# Monster_Moto_Shield.net
KiCad netlist of a schematic drawn in EAGLE
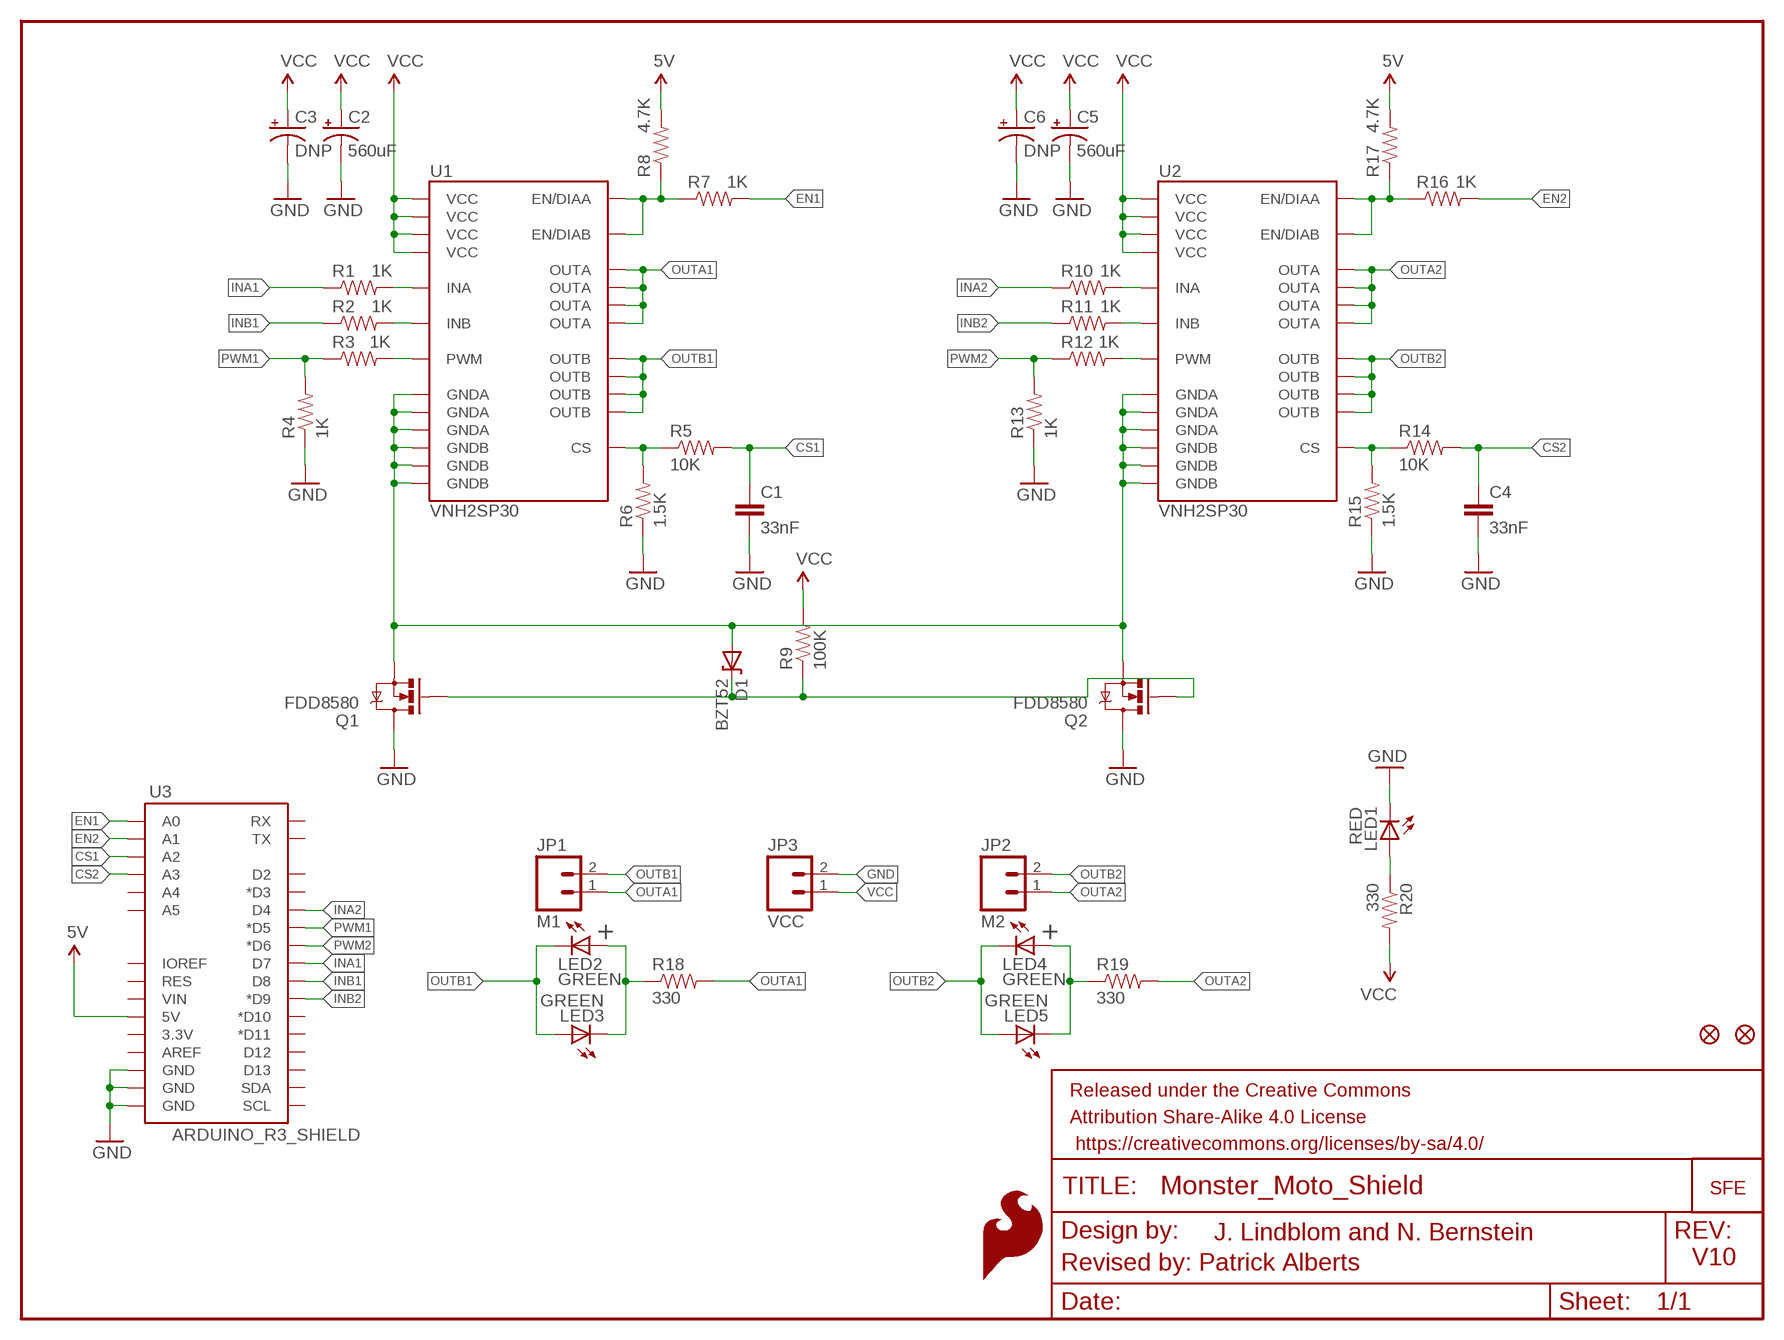
[diagram p0: schematic, sheet 1]

(export (version "E")
  (design (tool "Eeschema 10.0.6"))
  (components
    (comp (ref "C1")
      (value "33nF")
      (footprint "eagle-import:0603-CAP")
      (libsource (lib "eagle-import") (part "CAP0603-CAP"))
    )
    (comp (ref "C2")
      (value "560uF")
      (footprint "eagle-import:PANASONIC_G")
      (libsource (lib "eagle-import") (part "CAP_POLG"))
    )
    (comp (ref "C3")
      (value "DNP")
      (footprint "eagle-import:CPOL-RADIAL-1000UF-25V")
      (libsource (lib "eagle-import") (part "CAP_POLPTH4"))
    )
    (comp (ref "C4")
      (value "33nF")
      (footprint "eagle-import:0603-CAP")
      (libsource (lib "eagle-import") (part "CAP0603-CAP"))
    )
    (comp (ref "C5")
      (value "560uF")
      (footprint "eagle-import:PANASONIC_G")
      (libsource (lib "eagle-import") (part "CAP_POLG"))
    )
    (comp (ref "C6")
      (value "DNP")
      (footprint "eagle-import:CPOL-RADIAL-1000UF-25V")
      (libsource (lib "eagle-import") (part "CAP_POLPTH4"))
    )
    (comp (ref "D1")
      (value "BZT52")
      (footprint "eagle-import:SOD-323")
      (libsource (lib "eagle-import") (part "DIODE-ZENER-BZT52"))
    )
    (comp (ref "FRAME*")
      (value "FRAME-LETTER")
      (footprint "eagle-import:CREATIVE_COMMONS")
      (libsource (lib "eagle-import") (part "FRAME-LETTER"))
    )
    (comp (ref "JP1")
      (value "M1")
      (footprint "eagle-import:1X02_XTRA_BIG")
      (libsource (lib "eagle-import") (part "M02PTH4"))
    )
    (comp (ref "JP2")
      (value "M2")
      (footprint "eagle-import:1X02_XTRA_BIG")
      (libsource (lib "eagle-import") (part "M02PTH4"))
    )
    (comp (ref "JP3")
      (value "VCC")
      (footprint "eagle-import:1X02_XTRA_BIG")
      (libsource (lib "eagle-import") (part "M02PTH4"))
    )
    (comp (ref "JP4")
      (value "FIDUCIAL1X2")
      (footprint "eagle-import:FIDUCIAL-1X2")
      (libsource (lib "eagle-import") (part "FIDUCIAL1X2"))
    )
    (comp (ref "JP5")
      (value "LOGO-SFENEW")
      (footprint "eagle-import:SFE-NEW-WEBLOGO")
      (libsource (lib "eagle-import") (part "LOGO-SFENEW"))
    )
    (comp (ref "JP6")
      (value "FIDUCIAL1X2")
      (footprint "eagle-import:FIDUCIAL-1X2")
      (libsource (lib "eagle-import") (part "FIDUCIAL1X2"))
    )
    (comp (ref "LED1")
      (value "RED")
      (footprint "eagle-import:LED-0603")
      (libsource (lib "eagle-import") (part "LED-RED0603"))
    )
    (comp (ref "LED2")
      (value "GREEN")
      (footprint "eagle-import:LED-0603")
      (libsource (lib "eagle-import") (part "LED-GREEN0603"))
    )
    (comp (ref "LED3")
      (value "GREEN")
      (footprint "eagle-import:LED-0603")
      (libsource (lib "eagle-import") (part "LED-GREEN0603"))
    )
    (comp (ref "LED4")
      (value "GREEN")
      (footprint "eagle-import:LED-0603")
      (libsource (lib "eagle-import") (part "LED-GREEN0603"))
    )
    (comp (ref "LED5")
      (value "GREEN")
      (footprint "eagle-import:LED-0603")
      (libsource (lib "eagle-import") (part "LED-GREEN0603"))
    )
    (comp (ref "LOGO1")
      (value "SFE_LOGO_FLAME.2_INCH")
      (footprint "eagle-import:SFE_LOGO_FLAME_.2")
      (libsource (lib "eagle-import") (part "SFE_LOGO_FLAME.2_INCH"))
    )
    (comp (ref "Q1")
      (value "FDD8580")
      (footprint "eagle-import:DPAK")
      (libsource (lib "eagle-import") (part "MOSFET-NCHANNELFDD8580"))
    )
    (comp (ref "Q2")
      (value "FDD8580")
      (footprint "eagle-import:DPAK")
      (libsource (lib "eagle-import") (part "MOSFET-NCHANNELFDD8580"))
    )
    (comp (ref "R1")
      (value "1K")
      (footprint "eagle-import:0603-RES")
      (libsource (lib "eagle-import") (part "1KOHM1/10W1%(0603)"))
    )
    (comp (ref "R2")
      (value "1K")
      (footprint "eagle-import:0603-RES")
      (libsource (lib "eagle-import") (part "1KOHM1/10W1%(0603)"))
    )
    (comp (ref "R3")
      (value "1K")
      (footprint "eagle-import:0603-RES")
      (libsource (lib "eagle-import") (part "1KOHM1/10W1%(0603)"))
    )
    (comp (ref "R4")
      (value "1K")
      (footprint "eagle-import:0603-RES")
      (libsource (lib "eagle-import") (part "1KOHM1/10W1%(0603)"))
    )
    (comp (ref "R5")
      (value "10K")
      (footprint "eagle-import:0603-RES")
      (libsource (lib "eagle-import") (part "10KOHM1/10W1%(0603)0603"))
    )
    (comp (ref "R6")
      (value "1.5K")
      (footprint "eagle-import:0603")
      (libsource (lib "eagle-import") (part "1.5KOHM1/10W1%(0603)"))
    )
    (comp (ref "R7")
      (value "1K")
      (footprint "eagle-import:0603-RES")
      (libsource (lib "eagle-import") (part "1KOHM1/10W1%(0603)"))
    )
    (comp (ref "R8")
      (value "4.7K")
      (footprint "eagle-import:0603")
      (libsource (lib "eagle-import") (part "4.7KOHM1/10W1%(0603)"))
    )
    (comp (ref "R9")
      (value "100K")
      (footprint "eagle-import:0603-RES")
      (libsource (lib "eagle-import") (part "100KOHM1/10W1%(0603)"))
    )
    (comp (ref "R10")
      (value "1K")
      (footprint "eagle-import:0603-RES")
      (libsource (lib "eagle-import") (part "1KOHM1/10W1%(0603)"))
    )
    (comp (ref "R11")
      (value "1K")
      (footprint "eagle-import:0603-RES")
      (libsource (lib "eagle-import") (part "1KOHM1/10W1%(0603)"))
    )
    (comp (ref "R12")
      (value "1K")
      (footprint "eagle-import:0603-RES")
      (libsource (lib "eagle-import") (part "1KOHM1/10W1%(0603)"))
    )
    (comp (ref "R13")
      (value "1K")
      (footprint "eagle-import:0603-RES")
      (libsource (lib "eagle-import") (part "1KOHM1/10W1%(0603)"))
    )
    (comp (ref "R14")
      (value "10K")
      (footprint "eagle-import:0603-RES")
      (libsource (lib "eagle-import") (part "10KOHM1/10W1%(0603)0603"))
    )
    (comp (ref "R15")
      (value "1.5K")
      (footprint "eagle-import:0603")
      (libsource (lib "eagle-import") (part "1.5KOHM1/10W1%(0603)"))
    )
    (comp (ref "R16")
      (value "1K")
      (footprint "eagle-import:0603-RES")
      (libsource (lib "eagle-import") (part "1KOHM1/10W1%(0603)"))
    )
    (comp (ref "R17")
      (value "4.7K")
      (footprint "eagle-import:0603")
      (libsource (lib "eagle-import") (part "4.7KOHM1/10W1%(0603)"))
    )
    (comp (ref "R18")
      (value "330")
      (footprint "eagle-import:0603")
      (libsource (lib "eagle-import") (part "33OHM1/10W1%(0603)"))
    )
    (comp (ref "R19")
      (value "330")
      (footprint "eagle-import:0603")
      (libsource (lib "eagle-import") (part "33OHM1/10W1%(0603)"))
    )
    (comp (ref "R20")
      (value "330")
      (footprint "eagle-import:0603")
      (libsource (lib "eagle-import") (part "33OHM1/10W1%(0603)"))
    )
    (comp (ref "U1")
      (value "VNH2SP30")
      (footprint "eagle-import:VNH2SP30")
      (libsource (lib "eagle-import") (part "VNH2SP30"))
    )
    (comp (ref "U2")
      (value "VNH2SP30")
      (footprint "eagle-import:VNH2SP30")
      (libsource (lib "eagle-import") (part "VNH2SP30"))
    )
    (comp (ref "U3")
      (value "ARDUINO_R3_SHIELD")
      (footprint "eagle-import:UNO_R3_SHIELD")
      (libsource (lib "eagle-import") (part "ARDUINO_R3_SHIELD"))
    )
  )
  (nets
    (net (code "1") (name "5V") (class "Default")
      (node (ref "R17") (pin "2") (pinfunction "2_2") (pintype "passive"))
      (node (ref "R8") (pin "2") (pinfunction "2_2") (pintype "passive"))
      (node (ref "U3") (pin "5V") (pinfunction "5V_5V") (pintype "bidirectional"))
    )
    (net (code "2") (name "CS1") (class "Default")
      (node (ref "C1") (pin "1") (pinfunction "1_1") (pintype "passive"))
      (node (ref "R5") (pin "2") (pinfunction "2_2") (pintype "passive"))
      (node (ref "U3") (pin "A2") (pinfunction "A2_A2") (pintype "bidirectional"))
    )
    (net (code "3") (name "CS2") (class "Default")
      (node (ref "C4") (pin "1") (pinfunction "1_1") (pintype "passive"))
      (node (ref "R14") (pin "2") (pinfunction "2_2") (pintype "passive"))
      (node (ref "U3") (pin "A3") (pinfunction "A3_A3") (pintype "bidirectional"))
    )
    (net (code "4") (name "EN1") (class "Default")
      (node (ref "R7") (pin "2") (pinfunction "2_2") (pintype "passive"))
      (node (ref "U3") (pin "A0") (pinfunction "A0_A0") (pintype "bidirectional"))
    )
    (net (code "5") (name "EN2") (class "Default")
      (node (ref "R16") (pin "2") (pinfunction "2_2") (pintype "passive"))
      (node (ref "U3") (pin "A1") (pinfunction "A1_A1") (pintype "bidirectional"))
    )
    (net (code "6") (name "GND") (class "Default")
      (node (ref "C1") (pin "2") (pinfunction "2_2") (pintype "passive"))
      (node (ref "C2") (pin "-") (pinfunction "-_-") (pintype "passive"))
      (node (ref "C3") (pin "2") (pinfunction "-_2") (pintype "passive"))
      (node (ref "C4") (pin "2") (pinfunction "2_2") (pintype "passive"))
      (node (ref "C5") (pin "-") (pinfunction "-_-") (pintype "passive"))
      (node (ref "C6") (pin "2") (pinfunction "-_2") (pintype "passive"))
      (node (ref "JP3") (pin "2") (pinfunction "2_2") (pintype "passive"))
      (node (ref "LED1") (pin "C") (pinfunction "C_C") (pintype "passive"))
      (node (ref "Q1") (pin "4") (pinfunction "D_4") (pintype "passive"))
      (node (ref "Q2") (pin "4") (pinfunction "D_4") (pintype "passive"))
      (node (ref "R13") (pin "1") (pinfunction "1_1") (pintype "passive"))
      (node (ref "R15") (pin "1") (pinfunction "1_1") (pintype "passive"))
      (node (ref "R4") (pin "1") (pinfunction "1_1") (pintype "passive"))
      (node (ref "R6") (pin "1") (pinfunction "1_1") (pintype "passive"))
      (node (ref "U3") (pin "GND@0") (pinfunction "GND_GND@0") (pintype "bidirectional"))
      (node (ref "U3") (pin "GND@1") (pinfunction "GND_GND@1") (pintype "bidirectional"))
      (node (ref "U3") (pin "GND@2") (pinfunction "GND_GND@2") (pintype "bidirectional"))
    )
    (net (code "7") (name "INA1") (class "Default")
      (node (ref "R1") (pin "1") (pinfunction "1_1") (pintype "passive"))
      (node (ref "U3") (pin "D7") (pinfunction "D7_D7") (pintype "bidirectional"))
    )
    (net (code "8") (name "INA2") (class "Default")
      (node (ref "R10") (pin "1") (pinfunction "1_1") (pintype "passive"))
      (node (ref "U3") (pin "D4") (pinfunction "D4_D4") (pintype "bidirectional"))
    )
    (net (code "9") (name "INB1") (class "Default")
      (node (ref "R2") (pin "1") (pinfunction "1_1") (pintype "passive"))
      (node (ref "U3") (pin "D8") (pinfunction "D8_D8") (pintype "bidirectional"))
    )
    (net (code "10") (name "INB2") (class "Default")
      (node (ref "R11") (pin "1") (pinfunction "1_1") (pintype "passive"))
      (node (ref "U3") (pin "D9") (pinfunction "*D9_D9") (pintype "bidirectional"))
    )
    (net (code "11") (name "Net-(D1-A)") (class "Default")
      (node (ref "D1") (pin "2") (pinfunction "A_2") (pintype "passive"))
      (node (ref "Q1") (pin "3") (pinfunction "S_3") (pintype "passive"))
      (node (ref "Q2") (pin "3") (pinfunction "S_3") (pintype "passive"))
      (node (ref "U1") (pin "18") (pinfunction "GNDB_18") (pintype "bidirectional"))
      (node (ref "U1") (pin "19") (pinfunction "GNDB_19") (pintype "bidirectional"))
      (node (ref "U1") (pin "20") (pinfunction "GNDB_20") (pintype "bidirectional"))
      (node (ref "U1") (pin "26") (pinfunction "GNDA_26") (pintype "bidirectional"))
      (node (ref "U1") (pin "27") (pinfunction "GNDA_27") (pintype "bidirectional"))
      (node (ref "U1") (pin "28") (pinfunction "GNDA_28") (pintype "bidirectional"))
      (node (ref "U2") (pin "18") (pinfunction "GNDB_18") (pintype "bidirectional"))
      (node (ref "U2") (pin "19") (pinfunction "GNDB_19") (pintype "bidirectional"))
      (node (ref "U2") (pin "20") (pinfunction "GNDB_20") (pintype "bidirectional"))
      (node (ref "U2") (pin "26") (pinfunction "GNDA_26") (pintype "bidirectional"))
      (node (ref "U2") (pin "27") (pinfunction "GNDA_27") (pintype "bidirectional"))
      (node (ref "U2") (pin "28") (pinfunction "GNDA_28") (pintype "bidirectional"))
    )
    (net (code "12") (name "Net-(D1-C)") (class "Default")
      (node (ref "D1") (pin "1") (pinfunction "C_1") (pintype "passive"))
      (node (ref "Q1") (pin "1") (pinfunction "G_1") (pintype "passive"))
      (node (ref "Q2") (pin "1") (pinfunction "G_1") (pintype "passive"))
      (node (ref "R9") (pin "1") (pinfunction "1_1") (pintype "passive"))
    )
    (net (code "13") (name "Net-(LED1-PadA)") (class "Default")
      (node (ref "LED1") (pin "A") (pinfunction "A_A") (pintype "passive"))
      (node (ref "R20") (pin "1") (pinfunction "1_1") (pintype "passive"))
    )
    (net (code "14") (name "Net-(LED2-PadA)") (class "Default")
      (node (ref "LED2") (pin "A") (pinfunction "A_A") (pintype "passive"))
      (node (ref "LED3") (pin "C") (pinfunction "C_C") (pintype "passive"))
      (node (ref "R18") (pin "1") (pinfunction "1_1") (pintype "passive"))
    )
    (net (code "15") (name "Net-(LED4-PadA)") (class "Default")
      (node (ref "LED4") (pin "A") (pinfunction "A_A") (pintype "passive"))
      (node (ref "LED5") (pin "C") (pinfunction "C_C") (pintype "passive"))
      (node (ref "R19") (pin "1") (pinfunction "1_1") (pintype "passive"))
    )
    (net (code "16") (name "Net-(U1-CS)") (class "Default")
      (node (ref "R5") (pin "1") (pinfunction "1_1") (pintype "passive"))
      (node (ref "R6") (pin "2") (pinfunction "2_2") (pintype "passive"))
      (node (ref "U1") (pin "9") (pinfunction "CS_9") (pintype "bidirectional"))
    )
    (net (code "17") (name "Net-(U1-EN{slash}DIAA)") (class "Default")
      (node (ref "R7") (pin "1") (pinfunction "1_1") (pintype "passive"))
      (node (ref "R8") (pin "1") (pinfunction "1_1") (pintype "passive"))
      (node (ref "U1") (pin "10") (pinfunction "EN/DIAB_10") (pintype "bidirectional"))
      (node (ref "U1") (pin "6") (pinfunction "EN/DIAA_6") (pintype "bidirectional"))
    )
    (net (code "18") (name "Net-(U1-INA)") (class "Default")
      (node (ref "R1") (pin "2") (pinfunction "2_2") (pintype "passive"))
      (node (ref "U1") (pin "5") (pinfunction "INA_5") (pintype "bidirectional"))
    )
    (net (code "19") (name "Net-(U1-INB)") (class "Default")
      (node (ref "R2") (pin "2") (pinfunction "2_2") (pintype "passive"))
      (node (ref "U1") (pin "11") (pinfunction "INB_11") (pintype "bidirectional"))
    )
    (net (code "20") (name "Net-(U1-PWM)") (class "Default")
      (node (ref "R3") (pin "2") (pinfunction "2_2") (pintype "passive"))
      (node (ref "U1") (pin "8") (pinfunction "PWM_8") (pintype "bidirectional"))
    )
    (net (code "21") (name "Net-(U2-CS)") (class "Default")
      (node (ref "R14") (pin "1") (pinfunction "1_1") (pintype "passive"))
      (node (ref "R15") (pin "2") (pinfunction "2_2") (pintype "passive"))
      (node (ref "U2") (pin "9") (pinfunction "CS_9") (pintype "bidirectional"))
    )
    (net (code "22") (name "Net-(U2-EN{slash}DIAA)") (class "Default")
      (node (ref "R16") (pin "1") (pinfunction "1_1") (pintype "passive"))
      (node (ref "R17") (pin "1") (pinfunction "1_1") (pintype "passive"))
      (node (ref "U2") (pin "10") (pinfunction "EN/DIAB_10") (pintype "bidirectional"))
      (node (ref "U2") (pin "6") (pinfunction "EN/DIAA_6") (pintype "bidirectional"))
    )
    (net (code "23") (name "Net-(U2-INA)") (class "Default")
      (node (ref "R10") (pin "2") (pinfunction "2_2") (pintype "passive"))
      (node (ref "U2") (pin "5") (pinfunction "INA_5") (pintype "bidirectional"))
    )
    (net (code "24") (name "Net-(U2-INB)") (class "Default")
      (node (ref "R11") (pin "2") (pinfunction "2_2") (pintype "passive"))
      (node (ref "U2") (pin "11") (pinfunction "INB_11") (pintype "bidirectional"))
    )
    (net (code "25") (name "Net-(U2-PWM)") (class "Default")
      (node (ref "R12") (pin "2") (pinfunction "2_2") (pintype "passive"))
      (node (ref "U2") (pin "8") (pinfunction "PWM_8") (pintype "bidirectional"))
    )
    (net (code "26") (name "OUTA1") (class "Default")
      (node (ref "JP1") (pin "1") (pinfunction "1_1") (pintype "passive"))
      (node (ref "R18") (pin "2") (pinfunction "2_2") (pintype "passive"))
      (node (ref "U1") (pin "1") (pinfunction "OUTA_1") (pintype "bidirectional"))
      (node (ref "U1") (pin "25") (pinfunction "OUTA_25") (pintype "bidirectional"))
      (node (ref "U1") (pin "30") (pinfunction "OUTA_30") (pintype "bidirectional"))
      (node (ref "U1") (pin "SLUG3") (pinfunction "OUTA_SLUG3") (pintype "bidirectional"))
    )
    (net (code "27") (name "OUTA2") (class "Default")
      (node (ref "JP2") (pin "1") (pinfunction "1_1") (pintype "passive"))
      (node (ref "R19") (pin "2") (pinfunction "2_2") (pintype "passive"))
      (node (ref "U2") (pin "1") (pinfunction "OUTA_1") (pintype "bidirectional"))
      (node (ref "U2") (pin "25") (pinfunction "OUTA_25") (pintype "bidirectional"))
      (node (ref "U2") (pin "30") (pinfunction "OUTA_30") (pintype "bidirectional"))
      (node (ref "U2") (pin "SLUG3") (pinfunction "OUTA_SLUG3") (pintype "bidirectional"))
    )
    (net (code "28") (name "OUTB1") (class "Default")
      (node (ref "JP1") (pin "2") (pinfunction "2_2") (pintype "passive"))
      (node (ref "LED2") (pin "C") (pinfunction "C_C") (pintype "passive"))
      (node (ref "LED3") (pin "A") (pinfunction "A_A") (pintype "passive"))
      (node (ref "U1") (pin "15") (pinfunction "OUTB_15") (pintype "bidirectional"))
      (node (ref "U1") (pin "16") (pinfunction "OUTB_16") (pintype "bidirectional"))
      (node (ref "U1") (pin "21") (pinfunction "OUTB_21") (pintype "bidirectional"))
      (node (ref "U1") (pin "SLUG2") (pinfunction "OUTB_SLUG2") (pintype "bidirectional"))
    )
    (net (code "29") (name "OUTB2") (class "Default")
      (node (ref "JP2") (pin "2") (pinfunction "2_2") (pintype "passive"))
      (node (ref "LED4") (pin "C") (pinfunction "C_C") (pintype "passive"))
      (node (ref "LED5") (pin "A") (pinfunction "A_A") (pintype "passive"))
      (node (ref "U2") (pin "15") (pinfunction "OUTB_15") (pintype "bidirectional"))
      (node (ref "U2") (pin "16") (pinfunction "OUTB_16") (pintype "bidirectional"))
      (node (ref "U2") (pin "21") (pinfunction "OUTB_21") (pintype "bidirectional"))
      (node (ref "U2") (pin "SLUG2") (pinfunction "OUTB_SLUG2") (pintype "bidirectional"))
    )
    (net (code "30") (name "PWM1") (class "Default")
      (node (ref "R3") (pin "1") (pinfunction "1_1") (pintype "passive"))
      (node (ref "R4") (pin "2") (pinfunction "2_2") (pintype "passive"))
      (node (ref "U3") (pin "D5") (pinfunction "*D5_D5") (pintype "bidirectional"))
    )
    (net (code "31") (name "PWM2") (class "Default")
      (node (ref "R12") (pin "1") (pinfunction "1_1") (pintype "passive"))
      (node (ref "R13") (pin "2") (pinfunction "2_2") (pintype "passive"))
      (node (ref "U3") (pin "D6") (pinfunction "*D6_D6") (pintype "bidirectional"))
    )
    (net (code "32") (name "VCC") (class "Default")
      (node (ref "C2") (pin "+") (pinfunction "+_+") (pintype "passive"))
      (node (ref "C3") (pin "1") (pinfunction "+_1") (pintype "passive"))
      (node (ref "C5") (pin "+") (pinfunction "+_+") (pintype "passive"))
      (node (ref "C6") (pin "1") (pinfunction "+_1") (pintype "passive"))
      (node (ref "JP3") (pin "1") (pinfunction "1_1") (pintype "passive"))
      (node (ref "R20") (pin "2") (pinfunction "2_2") (pintype "passive"))
      (node (ref "R9") (pin "2") (pinfunction "2_2") (pintype "passive"))
      (node (ref "U1") (pin "13") (pinfunction "VCC_13") (pintype "bidirectional"))
      (node (ref "U1") (pin "23") (pinfunction "VCC_23") (pintype "bidirectional"))
      (node (ref "U1") (pin "3") (pinfunction "VCC_3") (pintype "bidirectional"))
      (node (ref "U1") (pin "SLUG1") (pinfunction "VCC_SLUG1") (pintype "bidirectional"))
      (node (ref "U2") (pin "13") (pinfunction "VCC_13") (pintype "bidirectional"))
      (node (ref "U2") (pin "23") (pinfunction "VCC_23") (pintype "bidirectional"))
      (node (ref "U2") (pin "3") (pinfunction "VCC_3") (pintype "bidirectional"))
      (node (ref "U2") (pin "SLUG1") (pinfunction "VCC_SLUG1") (pintype "bidirectional"))
    )
    (net (code "33") (name "unconnected-(U3-*D3-PadD3)") (class "Default")
      (node (ref "U3") (pin "D3") (pinfunction "*D3_D3") (pintype "bidirectional"))
    )
    (net (code "34") (name "unconnected-(U3-*D10-PadD10)") (class "Default")
      (node (ref "U3") (pin "D10") (pinfunction "*D10_D10") (pintype "bidirectional"))
    )
    (net (code "35") (name "unconnected-(U3-*D11-PadD11)") (class "Default")
      (node (ref "U3") (pin "D11") (pinfunction "*D11_D11") (pintype "bidirectional"))
    )
    (net (code "36") (name "unconnected-(U3-Pad3.3V)") (class "Default")
      (node (ref "U3") (pin "3.3V") (pinfunction "3.3V_3.3V") (pintype "bidirectional"))
    )
    (net (code "37") (name "unconnected-(U3-PadA4)") (class "Default")
      (node (ref "U3") (pin "A4") (pinfunction "A4_A4") (pintype "bidirectional"))
    )
    (net (code "38") (name "unconnected-(U3-PadA5)") (class "Default")
      (node (ref "U3") (pin "A5") (pinfunction "A5_A5") (pintype "bidirectional"))
    )
    (net (code "39") (name "unconnected-(U3-PadAREF)") (class "Default")
      (node (ref "U3") (pin "AREF") (pinfunction "AREF_AREF") (pintype "bidirectional"))
    )
    (net (code "40") (name "unconnected-(U3-PadD2)") (class "Default")
      (node (ref "U3") (pin "D2") (pinfunction "D2_D2") (pintype "bidirectional"))
    )
    (net (code "41") (name "unconnected-(U3-PadD12)") (class "Default")
      (node (ref "U3") (pin "D12") (pinfunction "D12_D12") (pintype "bidirectional"))
    )
    (net (code "42") (name "unconnected-(U3-PadD13)") (class "Default")
      (node (ref "U3") (pin "D13") (pinfunction "D13_D13") (pintype "bidirectional"))
    )
    (net (code "43") (name "unconnected-(U3-PadIOREF)") (class "Default")
      (node (ref "U3") (pin "IOREF") (pinfunction "IOREF_IOREF") (pintype "bidirectional"))
    )
    (net (code "44") (name "unconnected-(U3-PadRES)") (class "Default")
      (node (ref "U3") (pin "RES") (pinfunction "RES_RES") (pintype "bidirectional"))
    )
    (net (code "45") (name "unconnected-(U3-PadRX)") (class "Default")
      (node (ref "U3") (pin "RX") (pinfunction "RX_RX") (pintype "bidirectional"))
    )
    (net (code "46") (name "unconnected-(U3-PadSCL)") (class "Default")
      (node (ref "U3") (pin "SCL") (pinfunction "SCL_SCL") (pintype "bidirectional"))
    )
    (net (code "47") (name "unconnected-(U3-PadSDA)") (class "Default")
      (node (ref "U3") (pin "SDA") (pinfunction "SDA_SDA") (pintype "bidirectional"))
    )
    (net (code "48") (name "unconnected-(U3-PadTX)") (class "Default")
      (node (ref "U3") (pin "TX") (pinfunction "TX_TX") (pintype "bidirectional"))
    )
    (net (code "49") (name "unconnected-(U3-PadVIN)") (class "Default")
      (node (ref "U3") (pin "VIN") (pinfunction "VIN_VIN") (pintype "bidirectional"))
    )
  )
)
